# SCH_ROBOTIC_ARM_2022-05-08.net
KiCad netlist of a schematic drawn in EasyEDA
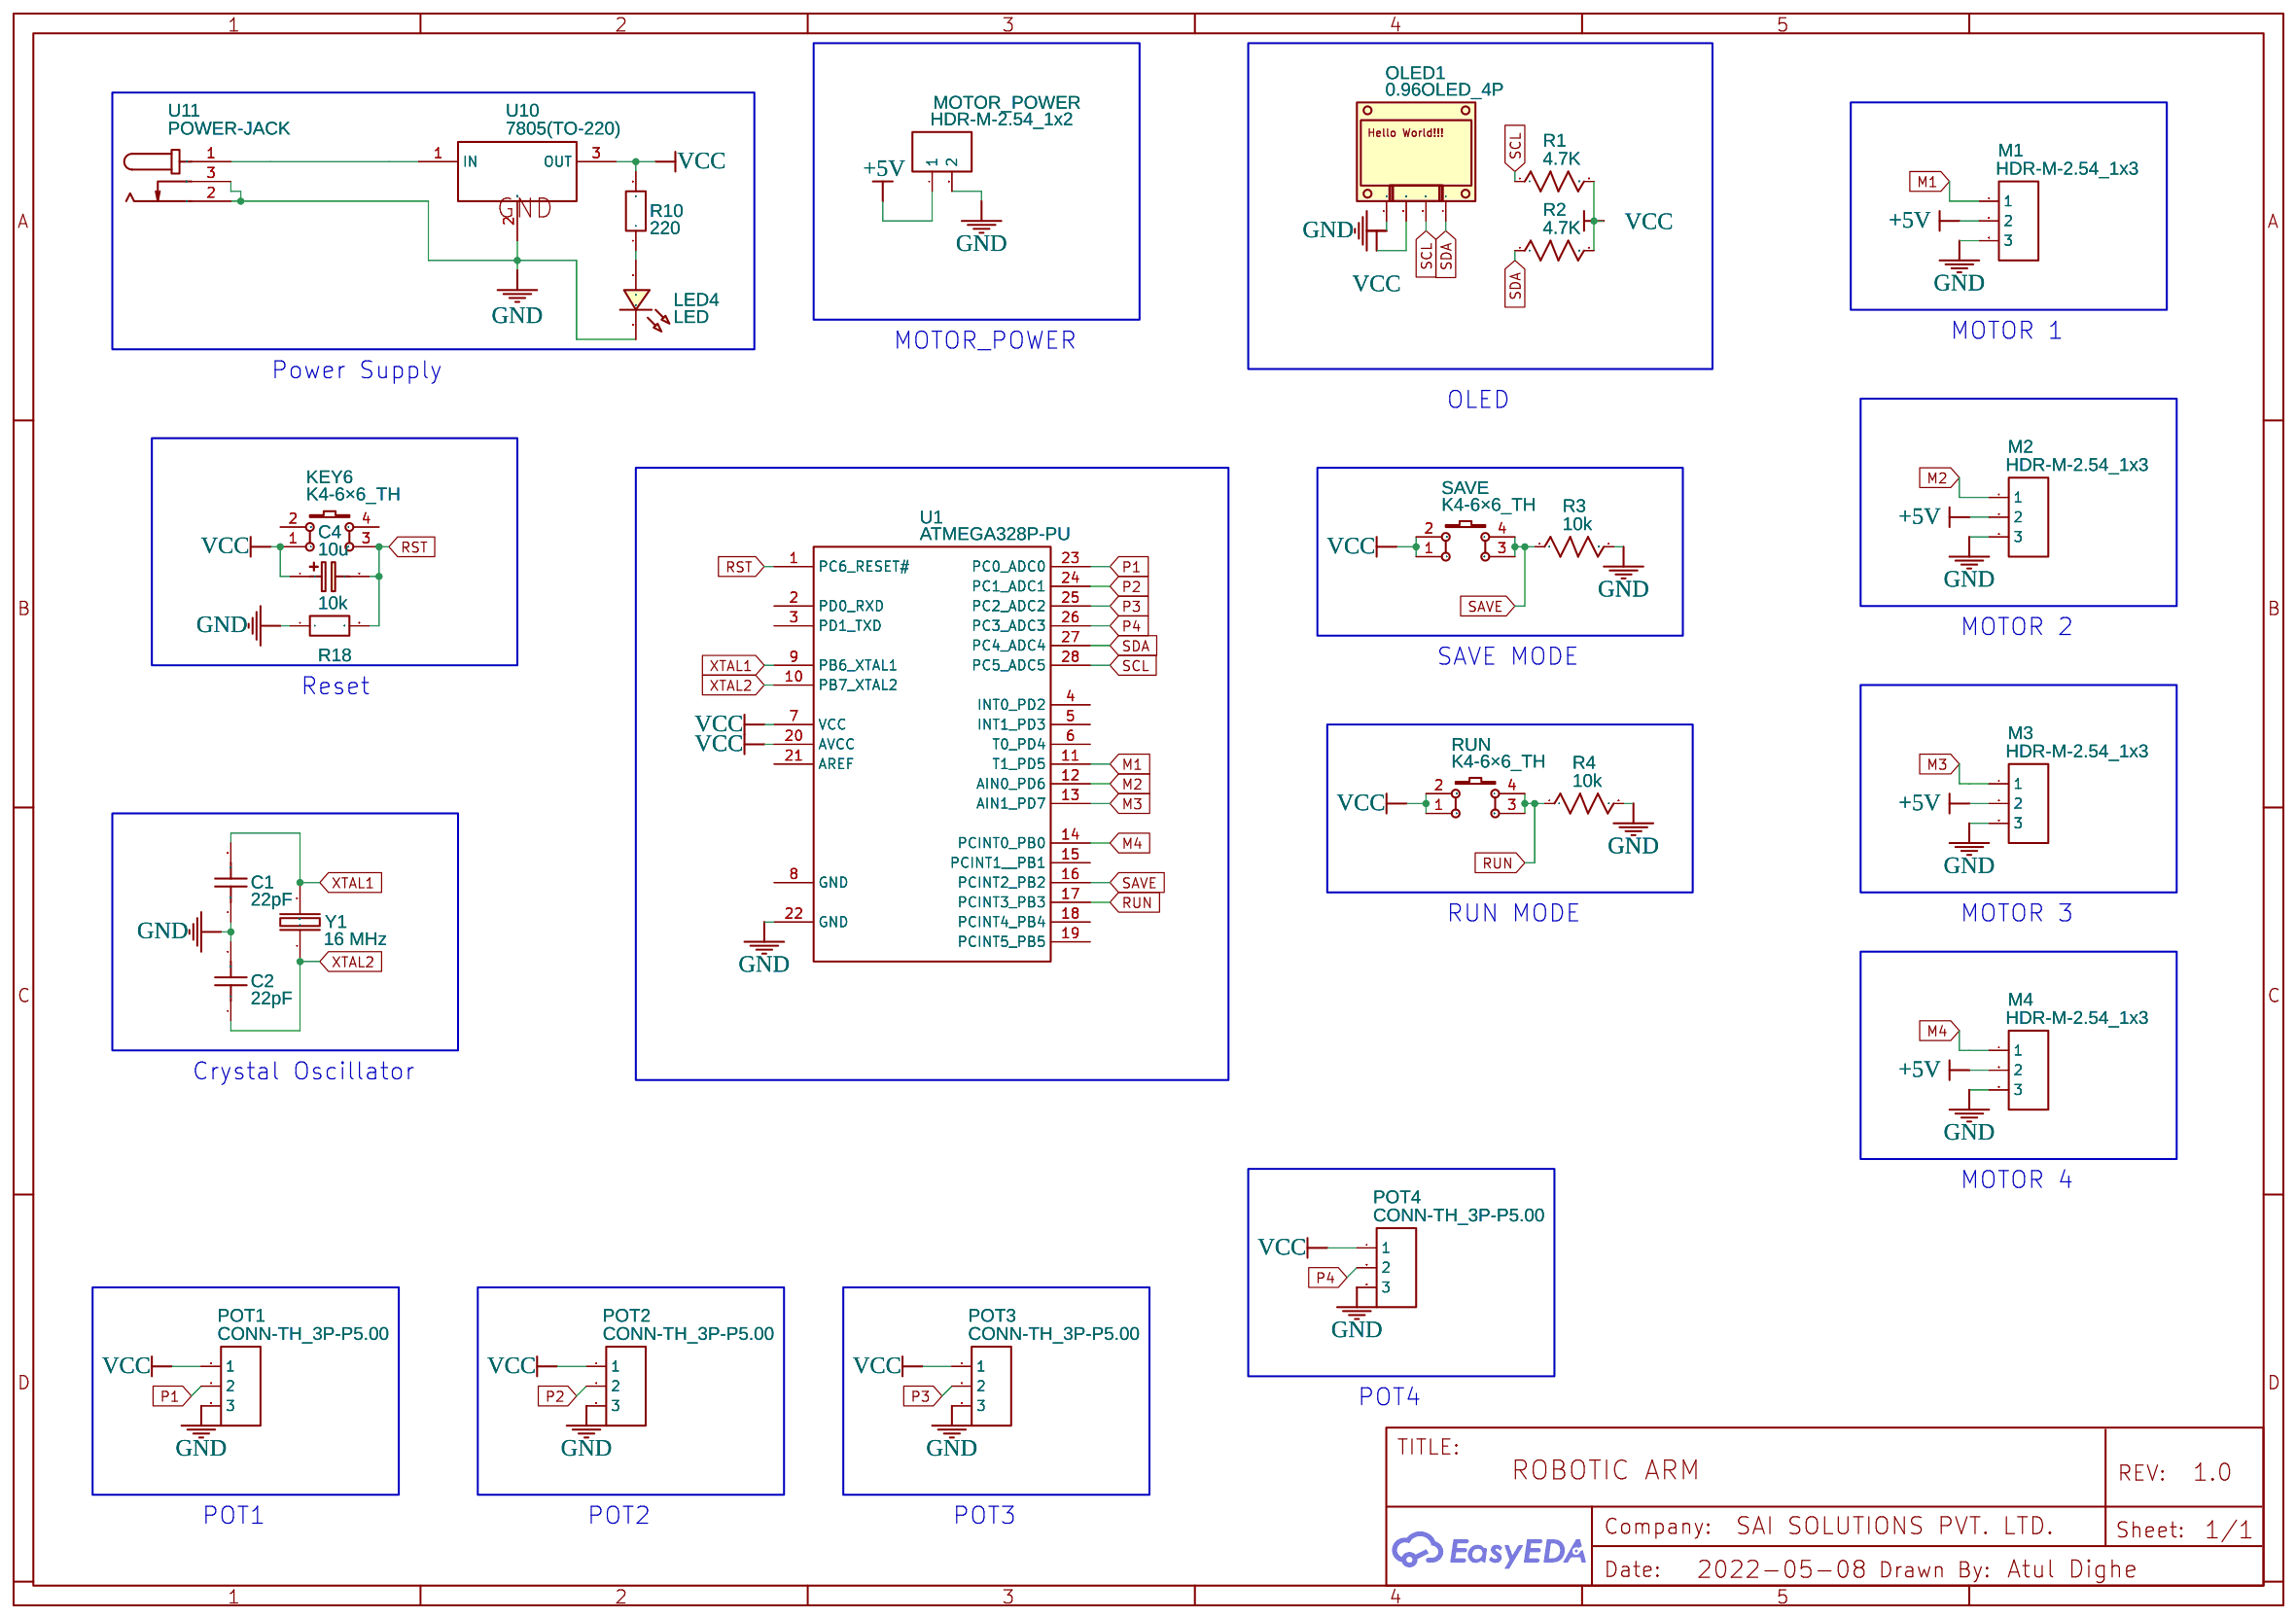
[diagram p0: schematic sheet]

(export (version "E")
  (design (tool "Eeschema 10.0.6"))
  (components
    (comp (ref "C1") (value "22pF") (libsource (lib "") (part "C_RAD-0.1_US")))
    (comp (ref "C2") (value "22pF") (libsource (lib "") (part "C_RAD-0.1_US")))
    (comp (ref "C4") (value "10u") (libsource (lib "") (part "CE_TH_D8.0×F3.5_EU")))
    (comp (ref "KEY6")
      (value "K4-6×6_TH")
      (fields
        (field (name "BOM_Manufacturer Part") "K2-1102DP-E4SW-04")
        (field (name "BOM_Supplier Part") "C136684")
      )
      (libsource (lib "") (part "K4-6×6_TH_1"))
    )
    (comp (ref "LED4")
      (value "LED")
      (fields
        (field (name "BOM_Manufacturer Part") "204-10SDRD/S530-A3-L")
        (field (name "BOM_Supplier Part") "C84774")
      )
      (libsource (lib "") (part "LED-TH-3mm_R"))
    )
    (comp (ref "M1")
      (value "HDR-M-2.54_1x3")
      (fields (field (name "BOM_Supplier Part") "C180248"))
      (libsource (lib "") (part "HDR-M-2.54_1x3"))
    )
    (comp (ref "M2")
      (value "HDR-M-2.54_1x3")
      (fields (field (name "BOM_Supplier Part") "C180248"))
      (libsource (lib "") (part "HDR-M-2.54_1x3"))
    )
    (comp (ref "M3")
      (value "HDR-M-2.54_1x3")
      (fields (field (name "BOM_Supplier Part") "C180248"))
      (libsource (lib "") (part "HDR-M-2.54_1x3"))
    )
    (comp (ref "M4")
      (value "HDR-M-2.54_1x3")
      (fields (field (name "BOM_Supplier Part") "C180248"))
      (libsource (lib "") (part "HDR-M-2.54_1x3"))
    )
    (comp (ref "MOTOR_POWER")
      (value "HDR-M-2.54_1x2")
      (fields (field (name "BOM_Supplier Part") "C124375"))
      (libsource (lib "") (part "HDR-M-2.54_1x2"))
    )
    (comp (ref "OLED1") (value "0.96OLED_4P") (libsource (lib "") (part "0.96OLED_4P")))
    (comp (ref "POT1") (value "CONN-TH_3P-P5.00") (libsource (lib "") (part "CONN-TH_3P-P5.00")))
    (comp (ref "POT2") (value "CONN-TH_3P-P5.00") (libsource (lib "") (part "CONN-TH_3P-P5.00")))
    (comp (ref "POT3") (value "CONN-TH_3P-P5.00") (libsource (lib "") (part "CONN-TH_3P-P5.00")))
    (comp (ref "POT4") (value "CONN-TH_3P-P5.00") (libsource (lib "") (part "CONN-TH_3P-P5.00")))
    (comp (ref "R1") (value "4.7K") (libsource (lib "") (part "R_AXIAL-0.4_US")))
    (comp (ref "R2") (value "4.7K") (libsource (lib "") (part "R_AXIAL-0.4_US")))
    (comp (ref "R3") (value "10k") (libsource (lib "") (part "R_AXIAL-0.4_US")))
    (comp (ref "R4") (value "10k") (libsource (lib "") (part "R_AXIAL-0.4_US")))
    (comp (ref "R10") (value "220") (libsource (lib "") (part "R_AXIAL-0.3_EU")))
    (comp (ref "R18") (value "10k") (libsource (lib "") (part "R_AXIAL-0.3_EU_1")))
    (comp (ref "RUN")
      (value "K4-6×6_TH")
      (fields
        (field (name "BOM_Manufacturer Part") "K2-1102DP-E4SW-04")
        (field (name "BOM_Supplier Part") "C136684")
      )
      (libsource (lib "") (part "K4-6×6_TH"))
    )
    (comp (ref "SAVE")
      (value "K4-6×6_TH")
      (fields
        (field (name "BOM_Manufacturer Part") "K2-1102DP-E4SW-04")
        (field (name "BOM_Supplier Part") "C136684")
      )
      (libsource (lib "") (part "K4-6×6_TH_2"))
    )
    (comp (ref "U1")
      (value "ATMEGA328P-PU")
      (fields (field (name "BOM_Supplier Part") "C33901"))
      (libsource (lib "") (part "ATMEGA328P-PU"))
    )
    (comp (ref "U10")
      (value "7805(TO-220)")
      (fields (field (name "BOM_Manufacturer Part") "L7805CV-DG") (field (name "BOM_Supplier Part") "C3795"))
      (libsource (lib "") (part "7805(TO-220)"))
    )
    (comp (ref "U11")
      (value "POWER-JACK")
      (fields (field (name "BOM_Supplier Part") "C9900001795"))
      (libsource (lib "") (part "POWER-JACK"))
    )
    (comp (ref "Y1") (value "16 MHz") (libsource (lib "") (part "?MHz")))
  )
  (nets
    (net (code "1") (name "+5V") (class "Default")
      (node (ref "M1") (pin "2") (pinfunction "2_2") (pintype "input"))
      (node (ref "M2") (pin "2") (pinfunction "2_2") (pintype "input"))
      (node (ref "M3") (pin "2") (pinfunction "2_2") (pintype "input"))
      (node (ref "M4") (pin "2") (pinfunction "2_2") (pintype "input"))
      (node (ref "MOTOR_POWER") (pin "1") (pinfunction "1_1") (pintype "unspecified"))
    )
    (net (code "2") (name "GND") (class "Default")
      (node (ref "C1") (pin "1") (pinfunction "1_1") (pintype "unspecified"))
      (node (ref "C2") (pin "2") (pinfunction "2_2") (pintype "unspecified"))
      (node (ref "LED4") (pin "2") (pinfunction "2_2") (pintype "unspecified"))
      (node (ref "M1") (pin "3") (pinfunction "3_3") (pintype "input"))
      (node (ref "M2") (pin "3") (pinfunction "3_3") (pintype "input"))
      (node (ref "M3") (pin "3") (pinfunction "3_3") (pintype "input"))
      (node (ref "M4") (pin "3") (pinfunction "3_3") (pintype "input"))
      (node (ref "MOTOR_POWER") (pin "2") (pinfunction "2_2") (pintype "unspecified"))
      (node (ref "OLED1") (pin "1") (pinfunction "1_1") (pintype "unspecified"))
      (node (ref "POT1") (pin "3") (pinfunction "3_3") (pintype "unspecified"))
      (node (ref "POT2") (pin "3") (pinfunction "3_3") (pintype "unspecified"))
      (node (ref "POT3") (pin "3") (pinfunction "3_3") (pintype "unspecified"))
      (node (ref "POT4") (pin "3") (pinfunction "3_3") (pintype "unspecified"))
      (node (ref "R18") (pin "1") (pinfunction "1_1") (pintype "unspecified"))
      (node (ref "R3") (pin "2") (pinfunction "2_2") (pintype "unspecified"))
      (node (ref "R4") (pin "2") (pinfunction "2_2") (pintype "unspecified"))
      (node (ref "U1") (pin "22") (pinfunction "GND_22") (pintype "passive"))
      (node (ref "U10") (pin "2") (pinfunction "GND_2") (pintype "passive"))
      (node (ref "U11") (pin "2") (pinfunction "2_2") (pintype "unspecified"))
      (node (ref "U11") (pin "3") (pinfunction "3_3") (pintype "unspecified"))
    )
    (net (code "3") (name "M1") (class "Default")
      (node (ref "M1") (pin "1") (pinfunction "1_1") (pintype "input"))
      (node (ref "U1") (pin "11") (pinfunction "T1_PD5_11") (pintype "bidirectional"))
    )
    (net (code "4") (name "M2") (class "Default")
      (node (ref "M2") (pin "1") (pinfunction "1_1") (pintype "input"))
      (node (ref "U1") (pin "12") (pinfunction "AIN0_PD6_12") (pintype "bidirectional"))
    )
    (net (code "5") (name "M3") (class "Default")
      (node (ref "M3") (pin "1") (pinfunction "1_1") (pintype "input"))
      (node (ref "U1") (pin "13") (pinfunction "AIN1_PD7_13") (pintype "bidirectional"))
    )
    (net (code "6") (name "M4") (class "Default")
      (node (ref "M4") (pin "1") (pinfunction "1_1") (pintype "input"))
      (node (ref "U1") (pin "14") (pinfunction "PCINT0_PB0_14") (pintype "bidirectional"))
    )
    (net (code "7") (name "Net-(LED4-Pad1)") (class "Default")
      (node (ref "LED4") (pin "1") (pinfunction "1_1") (pintype "unspecified"))
      (node (ref "R10") (pin "1") (pinfunction "1_1") (pintype "unspecified"))
    )
    (net (code "8") (name "Net-(U10-IN)") (class "Default")
      (node (ref "U10") (pin "1") (pinfunction "IN_1") (pintype "passive"))
      (node (ref "U11") (pin "1") (pinfunction "1_1") (pintype "unspecified"))
    )
    (net (code "9") (name "P1") (class "Default")
      (node (ref "POT1") (pin "2") (pinfunction "2_2") (pintype "unspecified"))
      (node (ref "U1") (pin "23") (pinfunction "PC0_ADC0_23") (pintype "bidirectional"))
    )
    (net (code "10") (name "P2") (class "Default")
      (node (ref "POT2") (pin "2") (pinfunction "2_2") (pintype "unspecified"))
      (node (ref "U1") (pin "24") (pinfunction "PC1_ADC1_24") (pintype "bidirectional"))
    )
    (net (code "11") (name "P3") (class "Default")
      (node (ref "POT3") (pin "2") (pinfunction "2_2") (pintype "unspecified"))
      (node (ref "U1") (pin "25") (pinfunction "PC2_ADC2_25") (pintype "bidirectional"))
    )
    (net (code "12") (name "P4") (class "Default")
      (node (ref "POT4") (pin "2") (pinfunction "2_2") (pintype "unspecified"))
      (node (ref "U1") (pin "26") (pinfunction "PC3_ADC3_26") (pintype "bidirectional"))
    )
    (net (code "13") (name "RST") (class "Default")
      (node (ref "C4") (pin "2") (pinfunction "2_2") (pintype "unspecified"))
      (node (ref "KEY6") (pin "3") (pinfunction "3_3") (pintype "unspecified"))
      (node (ref "R18") (pin "2") (pinfunction "2_2") (pintype "unspecified"))
      (node (ref "U1") (pin "1") (pinfunction "PC6_RESET#_1") (pintype "bidirectional"))
    )
    (net (code "14") (name "RUN") (class "Default")
      (node (ref "R4") (pin "1") (pinfunction "1_1") (pintype "unspecified"))
      (node (ref "RUN") (pin "3") (pinfunction "3_3") (pintype "unspecified"))
      (node (ref "RUN") (pin "4") (pinfunction "4_4") (pintype "unspecified"))
      (node (ref "U1") (pin "17") (pinfunction "PCINT3_PB3_17") (pintype "bidirectional"))
    )
    (net (code "15") (name "SAVE") (class "Default")
      (node (ref "R3") (pin "1") (pinfunction "1_1") (pintype "unspecified"))
      (node (ref "SAVE") (pin "3") (pinfunction "3_3") (pintype "unspecified"))
      (node (ref "SAVE") (pin "4") (pinfunction "4_4") (pintype "unspecified"))
      (node (ref "U1") (pin "16") (pinfunction "PCINT2_PB2_16") (pintype "bidirectional"))
    )
    (net (code "16") (name "SCL") (class "Default")
      (node (ref "OLED1") (pin "3") (pinfunction "3_3") (pintype "unspecified"))
      (node (ref "R1") (pin "1") (pinfunction "1_1") (pintype "unspecified"))
      (node (ref "U1") (pin "28") (pinfunction "PC5_ADC5_28") (pintype "bidirectional"))
    )
    (net (code "17") (name "SDA") (class "Default")
      (node (ref "OLED1") (pin "4") (pinfunction "4_4") (pintype "unspecified"))
      (node (ref "R2") (pin "1") (pinfunction "1_1") (pintype "unspecified"))
      (node (ref "U1") (pin "27") (pinfunction "PC4_ADC4_27") (pintype "bidirectional"))
    )
    (net (code "18") (name "VCC") (class "Default")
      (node (ref "C4") (pin "1") (pinfunction "1_1") (pintype "unspecified"))
      (node (ref "KEY6") (pin "1") (pinfunction "1_1") (pintype "unspecified"))
      (node (ref "OLED1") (pin "2") (pinfunction "2_2") (pintype "unspecified"))
      (node (ref "POT1") (pin "1") (pinfunction "1_1") (pintype "unspecified"))
      (node (ref "POT2") (pin "1") (pinfunction "1_1") (pintype "unspecified"))
      (node (ref "POT3") (pin "1") (pinfunction "1_1") (pintype "unspecified"))
      (node (ref "POT4") (pin "1") (pinfunction "1_1") (pintype "unspecified"))
      (node (ref "R1") (pin "2") (pinfunction "2_2") (pintype "unspecified"))
      (node (ref "R10") (pin "2") (pinfunction "2_2") (pintype "unspecified"))
      (node (ref "R2") (pin "2") (pinfunction "2_2") (pintype "unspecified"))
      (node (ref "RUN") (pin "1") (pinfunction "1_1") (pintype "unspecified"))
      (node (ref "RUN") (pin "2") (pinfunction "2_2") (pintype "unspecified"))
      (node (ref "SAVE") (pin "1") (pinfunction "1_1") (pintype "unspecified"))
      (node (ref "SAVE") (pin "2") (pinfunction "2_2") (pintype "unspecified"))
      (node (ref "U1") (pin "20") (pinfunction "AVCC_20") (pintype "passive"))
      (node (ref "U1") (pin "7") (pinfunction "VCC_7") (pintype "passive"))
      (node (ref "U10") (pin "3") (pinfunction "OUT_3") (pintype "passive"))
    )
    (net (code "19") (name "XTAL1") (class "Default")
      (node (ref "C1") (pin "2") (pinfunction "2_2") (pintype "unspecified"))
      (node (ref "U1") (pin "9") (pinfunction "PB6_XTAL1_9") (pintype "bidirectional"))
      (node (ref "Y1") (pin "2") (pinfunction "2_2") (pintype "unspecified"))
    )
    (net (code "20") (name "XTAL2") (class "Default")
      (node (ref "C2") (pin "1") (pinfunction "1_1") (pintype "unspecified"))
      (node (ref "U1") (pin "10") (pinfunction "PB7_XTAL2_10") (pintype "bidirectional"))
      (node (ref "Y1") (pin "1") (pinfunction "1_1") (pintype "unspecified"))
    )
    (net (code "21") (name "unconnected-(KEY6-Pad2)") (class "Default")
      (node (ref "KEY6") (pin "2") (pinfunction "2_2") (pintype "unspecified"))
    )
    (net (code "22") (name "unconnected-(KEY6-Pad4)") (class "Default")
      (node (ref "KEY6") (pin "4") (pinfunction "4_4") (pintype "unspecified"))
    )
    (net (code "23") (name "unconnected-(U1-AREF-Pad21)") (class "Default")
      (node (ref "U1") (pin "21") (pinfunction "AREF_21") (pintype "passive"))
    )
    (net (code "24") (name "unconnected-(U1-GND-Pad8)") (class "Default")
      (node (ref "U1") (pin "8") (pinfunction "GND_8") (pintype "passive"))
    )
    (net (code "25") (name "unconnected-(U1-INT0_PD2-Pad4)") (class "Default")
      (node (ref "U1") (pin "4") (pinfunction "INT0_PD2_4") (pintype "bidirectional"))
    )
    (net (code "26") (name "unconnected-(U1-INT1_PD3-Pad5)") (class "Default")
      (node (ref "U1") (pin "5") (pinfunction "INT1_PD3_5") (pintype "bidirectional"))
    )
    (net (code "27") (name "unconnected-(U1-PCINT1__PB1-Pad15)") (class "Default")
      (node (ref "U1") (pin "15") (pinfunction "PCINT1__PB1_15") (pintype "bidirectional"))
    )
    (net (code "28") (name "unconnected-(U1-PCINT4_PB4-Pad18)") (class "Default")
      (node (ref "U1") (pin "18") (pinfunction "PCINT4_PB4_18") (pintype "bidirectional"))
    )
    (net (code "29") (name "unconnected-(U1-PCINT5_PB5-Pad19)") (class "Default")
      (node (ref "U1") (pin "19") (pinfunction "PCINT5_PB5_19") (pintype "bidirectional"))
    )
    (net (code "30") (name "unconnected-(U1-PD0_RXD-Pad2)") (class "Default")
      (node (ref "U1") (pin "2") (pinfunction "PD0_RXD_2") (pintype "bidirectional"))
    )
    (net (code "31") (name "unconnected-(U1-PD1_TXD-Pad3)") (class "Default")
      (node (ref "U1") (pin "3") (pinfunction "PD1_TXD_3") (pintype "bidirectional"))
    )
    (net (code "32") (name "unconnected-(U1-T0_PD4-Pad6)") (class "Default")
      (node (ref "U1") (pin "6") (pinfunction "T0_PD4_6") (pintype "bidirectional"))
    )
  )
)
